# Powerboard_schematic.net
KiCad netlist of a schematic drawn in Altium Designer
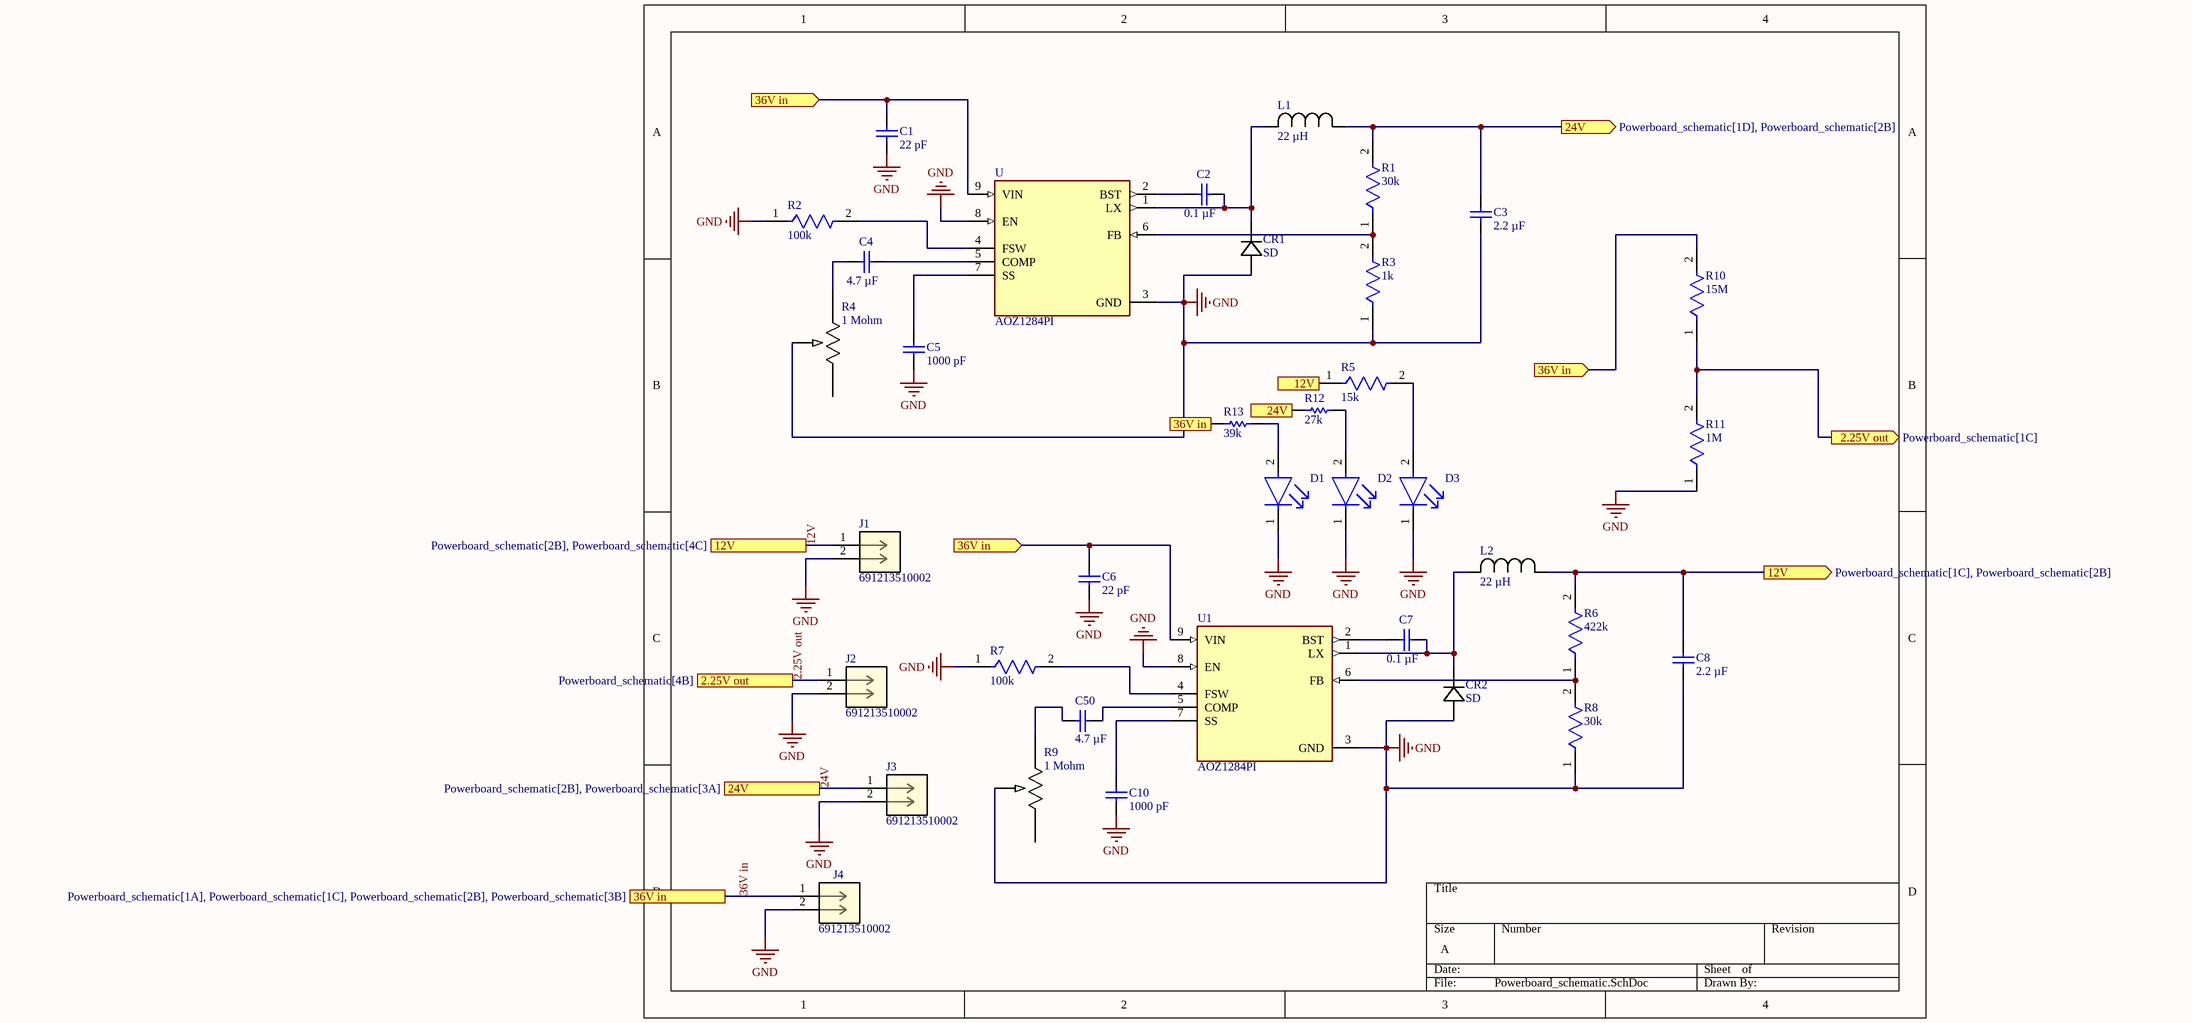
[diagram p0: Powerboard_schematic.SchDoc]

(export (version "E")
  (design (tool "Eeschema 10.0.6"))
  (components
    (comp (ref "C1")
      (value "22 pF")
      (footprint "CAPC2013X140X50NL20T25")
      (fields
        (field (name "PART NUMBER") "08055C104K4Z2A")
        (field (name "MANUFACTURER") "AVX Interconnect / Elco")
      )
      (libsource (lib "Altium Content Vault") (part "CAP"))
    )
    (comp (ref "C2")
      (value "0.1 µF")
      (footprint "CAPC2013X140X50NL20T25")
      (fields
        (field (name "PART NUMBER") "08055C104K4Z2A")
        (field (name "MANUFACTURER") "AVX Interconnect / Elco")
      )
      (libsource (lib "Altium Content Vault") (part "CAP"))
    )
    (comp (ref "C3")
      (value "2.2 µF")
      (footprint "CAPC2013X140X50NL20T25")
      (fields
        (field (name "PART NUMBER") "08055C104K4Z2A")
        (field (name "MANUFACTURER") "AVX Interconnect / Elco")
      )
      (libsource (lib "Altium Content Vault") (part "CAP"))
    )
    (comp (ref "C4")
      (value "4.7 µF")
      (footprint "CAPC2013X140X50NL20T25")
      (fields
        (field (name "PART NUMBER") "08055C104K4Z2A")
        (field (name "MANUFACTURER") "AVX Interconnect / Elco")
      )
      (libsource (lib "Altium Content Vault") (part "CAP"))
    )
    (comp (ref "C5")
      (value "1000 pF")
      (footprint "CAPC2013X140X50NL20T25")
      (fields
        (field (name "PART NUMBER") "08055C104K4Z2A")
        (field (name "MANUFACTURER") "AVX Interconnect / Elco")
      )
      (libsource (lib "Altium Content Vault") (part "CAP"))
    )
    (comp (ref "C6")
      (value "22 pF")
      (footprint "CAPC2013X140X50NL20T25")
      (fields
        (field (name "PART NUMBER") "08055C104K4Z2A")
        (field (name "MANUFACTURER") "AVX Interconnect / Elco")
      )
      (libsource (lib "Altium Content Vault") (part "CAP"))
    )
    (comp (ref "C7")
      (value "0.1 µF")
      (footprint "CAPC2013X140X50NL20T25")
      (fields
        (field (name "PART NUMBER") "08055C104K4Z2A")
        (field (name "MANUFACTURER") "AVX Interconnect / Elco")
      )
      (libsource (lib "Altium Content Vault") (part "CAP"))
    )
    (comp (ref "C8")
      (value "2.2 µF")
      (footprint "CAPC2013X140X50NL20T25")
      (fields
        (field (name "PART NUMBER") "08055C104K4Z2A")
        (field (name "MANUFACTURER") "AVX Interconnect / Elco")
      )
      (libsource (lib "Altium Content Vault") (part "CAP"))
    )
    (comp (ref "C10")
      (value "1000 pF")
      (footprint "CAPC2013X140X50NL20T25")
      (fields
        (field (name "PART NUMBER") "08055C104K4Z2A")
        (field (name "MANUFACTURER") "AVX Interconnect / Elco")
      )
      (libsource (lib "Altium Content Vault") (part "CAP"))
    )
    (comp (ref "C50")
      (value "4.7 µF")
      (footprint "CAPC2013X145X48ML20T23")
      (fields (field (name "MANUFACTURER") "Vitramon") (field (name "PART NUMBER") "VJ0805A1R0CXACW1BC"))
      (libsource (lib "Altium Content Vault") (part "CAP"))
    )
    (comp (ref "CR1")
      (value "SD")
      (footprint "SD2114_AVX")
      (description "No Description Available")
      (fields
        (field (name "MANUFACTURER_PART_NUMBER") "SD2114S040S8R0")
        (field (name "COPYRIGHT") "Copyright (C) 2022 Ultra Librarian. All rights reserved.")
      )
      (libsource (lib "SD2114S040S8R0") (part "SD2114S040S8R0"))
    )
    (comp (ref "CR2")
      (value "SD")
      (footprint "SD2114_AVX")
      (description "No Description Available")
      (fields
        (field (name "MANUFACTURER_PART_NUMBER") "SD2114S040S8R0")
        (field (name "COPYRIGHT") "Copyright (C) 2022 Ultra Librarian. All rights reserved.")
      )
      (libsource (lib "SD2114S040S8R0") (part "SD2114S040S8R0"))
    )
    (comp (ref "D1")
      (value "LTST-C171GKT")
      (footprint "FP-LTST-C171GKT-MFG")
      (description "LED GREEN CLEAR CHIP SMD")
      (libsource (lib "Altium Content Vault") (part "8706943c75ba83719d021d2fdc84c58"))
    )
    (comp (ref "D2")
      (value "LTST-C171GKT")
      (footprint "FP-LTST-C171GKT-MFG")
      (description "LED GREEN CLEAR CHIP SMD")
      (libsource (lib "Altium Content Vault") (part "8706943c75ba83719d021d2fdc84c58"))
    )
    (comp (ref "D3")
      (value "LTST-C171GKT")
      (footprint "FP-LTST-C171GKT-MFG")
      (description "LED GREEN CLEAR CHIP SMD")
      (libsource (lib "Altium Content Vault") (part "8706943c75ba83719d021d2fdc84c58"))
    )
    (comp (ref "J1")
      (value "691213510002")
      (footprint "CONN_691213510002_WRE")
      (description "No Description Available")
      (fields (field (name "COPYRIGHT") "Copyright (C) 2023 Ultra Librarian. All rights reserved."))
      (libsource (lib "691213510002") (part "691213510002"))
    )
    (comp (ref "J2")
      (value "691213510002")
      (footprint "CONN_691213510002_WRE")
      (description "No Description Available")
      (fields (field (name "COPYRIGHT") "Copyright (C) 2023 Ultra Librarian. All rights reserved."))
      (libsource (lib "691213510002") (part "691213510002"))
    )
    (comp (ref "J3")
      (value "691213510002")
      (footprint "CONN_691213510002_WRE")
      (description "No Description Available")
      (fields (field (name "COPYRIGHT") "Copyright (C) 2023 Ultra Librarian. All rights reserved."))
      (libsource (lib "691213510002") (part "691213510002"))
    )
    (comp (ref "J4")
      (value "691213510002")
      (footprint "CONN_691213510002_WRE")
      (description "No Description Available")
      (fields (field (name "COPYRIGHT") "Copyright (C) 2023 Ultra Librarian. All rights reserved."))
      (libsource (lib "691213510002") (part "691213510002"))
    )
    (comp (ref "L1")
      (value "22 µH")
      (footprint "IND_CTDO1813PF-223HC_CTH")
      (description "No Description Available")
      (fields
        (field (name "MANUFACTURER_PART_NUMBER") "CTDO1813PF-223HC")
        (field (name "COPYRIGHT") "Copyright (C) 2023 Ultra Librarian. All rights reserved.")
      )
      (libsource (lib "CTDO1813PF-223HC") (part "CTDO1813PF-223HC"))
    )
    (comp (ref "L2")
      (value "22 µH")
      (footprint "IND_CTDO1813PF-223HC_CTH")
      (description "No Description Available")
      (fields
        (field (name "MANUFACTURER_PART_NUMBER") "CTDO1813PF-223HC")
        (field (name "COPYRIGHT") "Copyright (C) 2023 Ultra Librarian. All rights reserved.")
      )
      (libsource (lib "CTDO1813PF-223HC") (part "CTDO1813PF-223HC"))
    )
    (comp (ref "R1")
      (value "30k")
      (footprint "FP-CRCW0805-e3-IPC_B")
      (description "RES Thick Film, 1MΩ, 1%, 0.125W, 100ppm/°C, 0805")
      (fields (field (name "TOLERANCE") "1%"))
      (libsource (lib "Altium Content Vault") (part "1029c3af85768c4190bb7ad29bc67b5"))
    )
    (comp (ref "R2")
      (value "100k")
      (footprint "FP-CRCW0805-e3-IPC_B")
      (description "RES Thick Film, 1MΩ, 1%, 0.125W, 100ppm/°C, 0805")
      (fields (field (name "TOLERANCE") "1%"))
      (libsource (lib "Altium Content Vault") (part "1029c3af85768c4190bb7ad29bc67b5"))
    )
    (comp (ref "R3")
      (value "1k")
      (footprint "FP-CRCW0805-e3-IPC_B")
      (description "RES Thick Film, 1MΩ, 1%, 0.125W, 100ppm/°C, 0805")
      (fields (field (name "TOLERANCE") "1%"))
      (libsource (lib "Altium Content Vault") (part "1029c3af85768c4190bb7ad29bc67b5"))
    )
    (comp (ref "R4")
      (value "1 Mohm")
      (footprint "TRIM_PV36W105C01B00")
      (description "No Description Available")
      (fields
        (field (name "MANUFACTURER_PART_NUMBER") "PV36W105C01B00")
        (field (name "COPYRIGHT") "Copyright (C) 2022 Ultra Librarian. All rights reserved.")
      )
      (libsource (lib "PV36W105C01B00") (part "PV36W105C01B00"))
    )
    (comp (ref "R5")
      (value "15k")
      (footprint "FP-RN732A-MFG")
      (fields
        (field (name "OCTOPART") "https://octopart.com/rn73c2a15kb-te+connectivity-47108263")
        (field (name "MANUFACTURER") "TE Connectivity")
        (field (name "TOLERANCE") "0.1%")
      )
      (libsource (lib "Altium Content Vault") (part "1029c3af85768c4190bb7ad29bc67b5"))
    )
    (comp (ref "R6")
      (value "422k")
      (footprint "FP-CRCW0805-e3-IPC_B")
      (description "RES Thick Film, 1MΩ, 1%, 0.125W, 100ppm/°C, 0805")
      (fields (field (name "TOLERANCE") "1%"))
      (libsource (lib "Altium Content Vault") (part "1029c3af85768c4190bb7ad29bc67b5"))
    )
    (comp (ref "R7")
      (value "100k")
      (footprint "FP-CRCW0805-e3-IPC_B")
      (description "RES Thick Film, 1MΩ, 1%, 0.125W, 100ppm/°C, 0805")
      (fields (field (name "TOLERANCE") "1%"))
      (libsource (lib "Altium Content Vault") (part "1029c3af85768c4190bb7ad29bc67b5"))
    )
    (comp (ref "R8")
      (value "30k")
      (footprint "FP-CRCW0805-e3-IPC_B")
      (description "RES Thick Film, 1MΩ, 1%, 0.125W, 100ppm/°C, 0805")
      (fields (field (name "TOLERANCE") "1%"))
      (libsource (lib "Altium Content Vault") (part "1029c3af85768c4190bb7ad29bc67b5"))
    )
    (comp (ref "R9")
      (value "1 Mohm")
      (footprint "TRIM_PV36W105C01B00")
      (description "No Description Available")
      (fields
        (field (name "MANUFACTURER_PART_NUMBER") "PV36W105C01B00")
        (field (name "COPYRIGHT") "Copyright (C) 2022 Ultra Librarian. All rights reserved.")
      )
      (libsource (lib "PV36W105C01B00") (part "PV36W105C01B00"))
    )
    (comp (ref "R10")
      (value "15M")
      (footprint "FP-CRCW0805-e3-IPC_B")
      (description "RES Thick Film, 1MΩ, 1%, 0.125W, 100ppm/°C, 0805")
      (fields (field (name "TOLERANCE") "1%"))
      (libsource (lib "Altium Content Vault") (part "1029c3af85768c4190bb7ad29bc67b5"))
    )
    (comp (ref "R11")
      (value "1M")
      (footprint "FP-CRCW0805-e3-IPC_B")
      (description "RES Thick Film, 1MΩ, 1%, 0.125W, 100ppm/°C, 0805")
      (fields (field (name "TOLERANCE") "1%"))
      (libsource (lib "Altium Content Vault") (part "1029c3af85768c4190bb7ad29bc67b5"))
    )
    (comp (ref "R12")
      (value "27k")
      (footprint "RESC2013X60X40NL20T25")
      (description "ERA-6AED273V")
      (fields (field (name "MANUFACTURER") "Panasonic"))
      (libsource (lib "Altium Content Vault") (part "RES"))
    )
    (comp (ref "R13")
      (value "39k")
      (footprint "RESC2013X60X40LL20T25")
      (description "ERA6AEB393V")
      (fields (field (name "MANUFACTURER") "Panasonic"))
      (libsource (lib "Altium Content Vault") (part "RES"))
    )
    (comp (ref "U")
      (value "AOZ1284PI")
      (footprint "SOP127P600X170-9N")
      (fields (field (name "MF") "Alpha &"))
      (libsource (lib "AOZ1284PI") (part "AOZ1284PI"))
    )
    (comp (ref "U1")
      (value "AOZ1284PI")
      (footprint "SOP127P600X170-9N")
      (fields (field (name "MF") "Alpha &"))
      (libsource (lib "AOZ1284PI") (part "AOZ1284PI"))
    )
  )
  (nets
    (net (code "1") (name "/2.25V out") (class "Default")
      (node (ref "J2") (pin "1") (pinfunction "1_1") (pintype "passive"))
      (node (ref "R10") (pin "1") (pinfunction "1_1") (pintype "passive"))
      (node (ref "R11") (pin "2") (pinfunction "2_2") (pintype "passive"))
    )
    (net (code "2") (name "/12V") (class "Default")
      (node (ref "C8") (pin "2") (pinfunction "2_2") (pintype "passive"))
      (node (ref "J1") (pin "1") (pinfunction "1_1") (pintype "passive"))
      (node (ref "L2") (pin "1") (pinfunction "1_1") (pintype "passive"))
      (node (ref "R5") (pin "1") (pinfunction "1_1") (pintype "passive"))
      (node (ref "R6") (pin "2") (pinfunction "2_2") (pintype "passive"))
    )
    (net (code "3") (name "/24V") (class "Default")
      (node (ref "C3") (pin "2") (pinfunction "2_2") (pintype "passive"))
      (node (ref "J3") (pin "1") (pinfunction "1_1") (pintype "passive"))
      (node (ref "L1") (pin "1") (pinfunction "1_1") (pintype "passive"))
      (node (ref "R1") (pin "2") (pinfunction "2_2") (pintype "passive"))
      (node (ref "R12") (pin "1") (pinfunction "1_1") (pintype "passive"))
    )
    (net (code "4") (name "/36V in") (class "Default")
      (node (ref "C1") (pin "2") (pinfunction "2_2") (pintype "passive"))
      (node (ref "C6") (pin "2") (pinfunction "2_2") (pintype "passive"))
      (node (ref "J4") (pin "1") (pinfunction "1_1") (pintype "passive"))
      (node (ref "R10") (pin "2") (pinfunction "2_2") (pintype "passive"))
      (node (ref "R13") (pin "1") (pinfunction "1_1") (pintype "passive"))
      (node (ref "U") (pin "9") (pinfunction "VIN_9") (pintype "input"))
      (node (ref "U1") (pin "9") (pinfunction "VIN_9") (pintype "input"))
    )
    (net (code "5") (name "GND") (class "Default")
      (node (ref "C1") (pin "1") (pinfunction "1_1") (pintype "passive"))
      (node (ref "C10") (pin "1") (pinfunction "1_1") (pintype "passive"))
      (node (ref "C3") (pin "1") (pinfunction "1_1") (pintype "passive"))
      (node (ref "C5") (pin "1") (pinfunction "1_1") (pintype "passive"))
      (node (ref "C6") (pin "1") (pinfunction "1_1") (pintype "passive"))
      (node (ref "C8") (pin "1") (pinfunction "1_1") (pintype "passive"))
      (node (ref "CR1") (pin "2") (pinfunction "12_2") (pintype "passive"))
      (node (ref "CR2") (pin "2") (pinfunction "12_2") (pintype "passive"))
      (node (ref "D1") (pin "1") (pinfunction "C_1") (pintype "passive"))
      (node (ref "D2") (pin "1") (pinfunction "C_1") (pintype "passive"))
      (node (ref "D3") (pin "1") (pinfunction "C_1") (pintype "passive"))
      (node (ref "J1") (pin "2") (pinfunction "2_2") (pintype "passive"))
      (node (ref "J2") (pin "2") (pinfunction "2_2") (pintype "passive"))
      (node (ref "J3") (pin "2") (pinfunction "2_2") (pintype "passive"))
      (node (ref "J4") (pin "2") (pinfunction "2_2") (pintype "passive"))
      (node (ref "R11") (pin "1") (pinfunction "1_1") (pintype "passive"))
      (node (ref "R2") (pin "1") (pinfunction "1_1") (pintype "passive"))
      (node (ref "R3") (pin "1") (pinfunction "1_1") (pintype "passive"))
      (node (ref "R4") (pin "2") (pinfunction "2_2") (pintype "passive"))
      (node (ref "R7") (pin "1") (pinfunction "1_1") (pintype "passive"))
      (node (ref "R8") (pin "1") (pinfunction "1_1") (pintype "passive"))
      (node (ref "R9") (pin "2") (pinfunction "2_2") (pintype "passive"))
      (node (ref "U") (pin "3") (pinfunction "GND_3") (pintype "power_in"))
      (node (ref "U") (pin "8") (pinfunction "EN_8") (pintype "input"))
      (node (ref "U1") (pin "3") (pinfunction "GND_3") (pintype "power_in"))
      (node (ref "U1") (pin "8") (pinfunction "EN_8") (pintype "input"))
    )
    (net (code "6") (name "Net-(C4-Pad2)") (class "Default")
      (node (ref "C4") (pin "2") (pinfunction "2_2") (pintype "passive"))
      (node (ref "R4") (pin "3") (pinfunction "3_3") (pintype "passive"))
    )
    (net (code "7") (name "Net-(C50-Pad1)") (class "Default")
      (node (ref "C50") (pin "1") (pinfunction "1_1") (pintype "passive"))
      (node (ref "R9") (pin "3") (pinfunction "3_3") (pintype "passive"))
    )
    (net (code "8") (name "Net-(CR1-11)") (class "Default")
      (node (ref "C2") (pin "2") (pinfunction "2_2") (pintype "passive"))
      (node (ref "CR1") (pin "1") (pinfunction "11_1") (pintype "passive"))
      (node (ref "L1") (pin "2") (pinfunction "2_2") (pintype "passive"))
      (node (ref "U") (pin "1") (pinfunction "LX_1") (pintype "output"))
    )
    (net (code "9") (name "Net-(CR2-11)") (class "Default")
      (node (ref "C7") (pin "2") (pinfunction "2_2") (pintype "passive"))
      (node (ref "CR2") (pin "1") (pinfunction "11_1") (pintype "passive"))
      (node (ref "L2") (pin "2") (pinfunction "2_2") (pintype "passive"))
      (node (ref "U1") (pin "1") (pinfunction "LX_1") (pintype "output"))
    )
    (net (code "10") (name "Net-(D1-A)") (class "Default")
      (node (ref "D1") (pin "2") (pinfunction "A_2") (pintype "passive"))
      (node (ref "R13") (pin "2") (pinfunction "2_2") (pintype "passive"))
    )
    (net (code "11") (name "Net-(D2-A)") (class "Default")
      (node (ref "D2") (pin "2") (pinfunction "A_2") (pintype "passive"))
      (node (ref "R12") (pin "2") (pinfunction "2_2") (pintype "passive"))
    )
    (net (code "12") (name "Net-(D3-A)") (class "Default")
      (node (ref "D3") (pin "2") (pinfunction "A_2") (pintype "passive"))
      (node (ref "R5") (pin "2") (pinfunction "2_2") (pintype "passive"))
    )
    (net (code "13") (name "Net-(U-BST)") (class "Default")
      (node (ref "C2") (pin "1") (pinfunction "1_1") (pintype "passive"))
      (node (ref "U") (pin "2") (pinfunction "BST_2") (pintype "output"))
    )
    (net (code "14") (name "Net-(U-COMP)") (class "Default")
      (node (ref "C4") (pin "1") (pinfunction "1_1") (pintype "passive"))
      (node (ref "U") (pin "5") (pinfunction "COMP_5") (pintype "passive"))
    )
    (net (code "15") (name "Net-(U-FB)") (class "Default")
      (node (ref "R1") (pin "1") (pinfunction "1_1") (pintype "passive"))
      (node (ref "R3") (pin "2") (pinfunction "2_2") (pintype "passive"))
      (node (ref "U") (pin "6") (pinfunction "FB_6") (pintype "input"))
    )
    (net (code "16") (name "Net-(U-FSW)") (class "Default")
      (node (ref "R2") (pin "2") (pinfunction "2_2") (pintype "passive"))
      (node (ref "U") (pin "4") (pinfunction "FSW_4") (pintype "passive"))
    )
    (net (code "17") (name "Net-(U-SS)") (class "Default")
      (node (ref "C5") (pin "2") (pinfunction "2_2") (pintype "passive"))
      (node (ref "U") (pin "7") (pinfunction "SS_7") (pintype "passive"))
    )
    (net (code "18") (name "Net-(U1-BST)") (class "Default")
      (node (ref "C7") (pin "1") (pinfunction "1_1") (pintype "passive"))
      (node (ref "U1") (pin "2") (pinfunction "BST_2") (pintype "output"))
    )
    (net (code "19") (name "Net-(U1-COMP)") (class "Default")
      (node (ref "C50") (pin "2") (pinfunction "2_2") (pintype "passive"))
      (node (ref "U1") (pin "5") (pinfunction "COMP_5") (pintype "passive"))
    )
    (net (code "20") (name "Net-(U1-FB)") (class "Default")
      (node (ref "R6") (pin "1") (pinfunction "1_1") (pintype "passive"))
      (node (ref "R8") (pin "2") (pinfunction "2_2") (pintype "passive"))
      (node (ref "U1") (pin "6") (pinfunction "FB_6") (pintype "input"))
    )
    (net (code "21") (name "Net-(U1-FSW)") (class "Default")
      (node (ref "R7") (pin "2") (pinfunction "2_2") (pintype "passive"))
      (node (ref "U1") (pin "4") (pinfunction "FSW_4") (pintype "passive"))
    )
    (net (code "22") (name "Net-(U1-SS)") (class "Default")
      (node (ref "C10") (pin "2") (pinfunction "2_2") (pintype "passive"))
      (node (ref "U1") (pin "7") (pinfunction "SS_7") (pintype "passive"))
    )
    (net (code "23") (name "unconnected-(R4-Pad1)") (class "Default")
      (node (ref "R4") (pin "1") (pinfunction "1_1") (pintype "passive"))
    )
    (net (code "24") (name "unconnected-(R9-Pad1)") (class "Default")
      (node (ref "R9") (pin "1") (pinfunction "1_1") (pintype "passive"))
    )
  )
)
